# M1_Design.net
KiCad netlist of a schematic drawn in Altium Designer
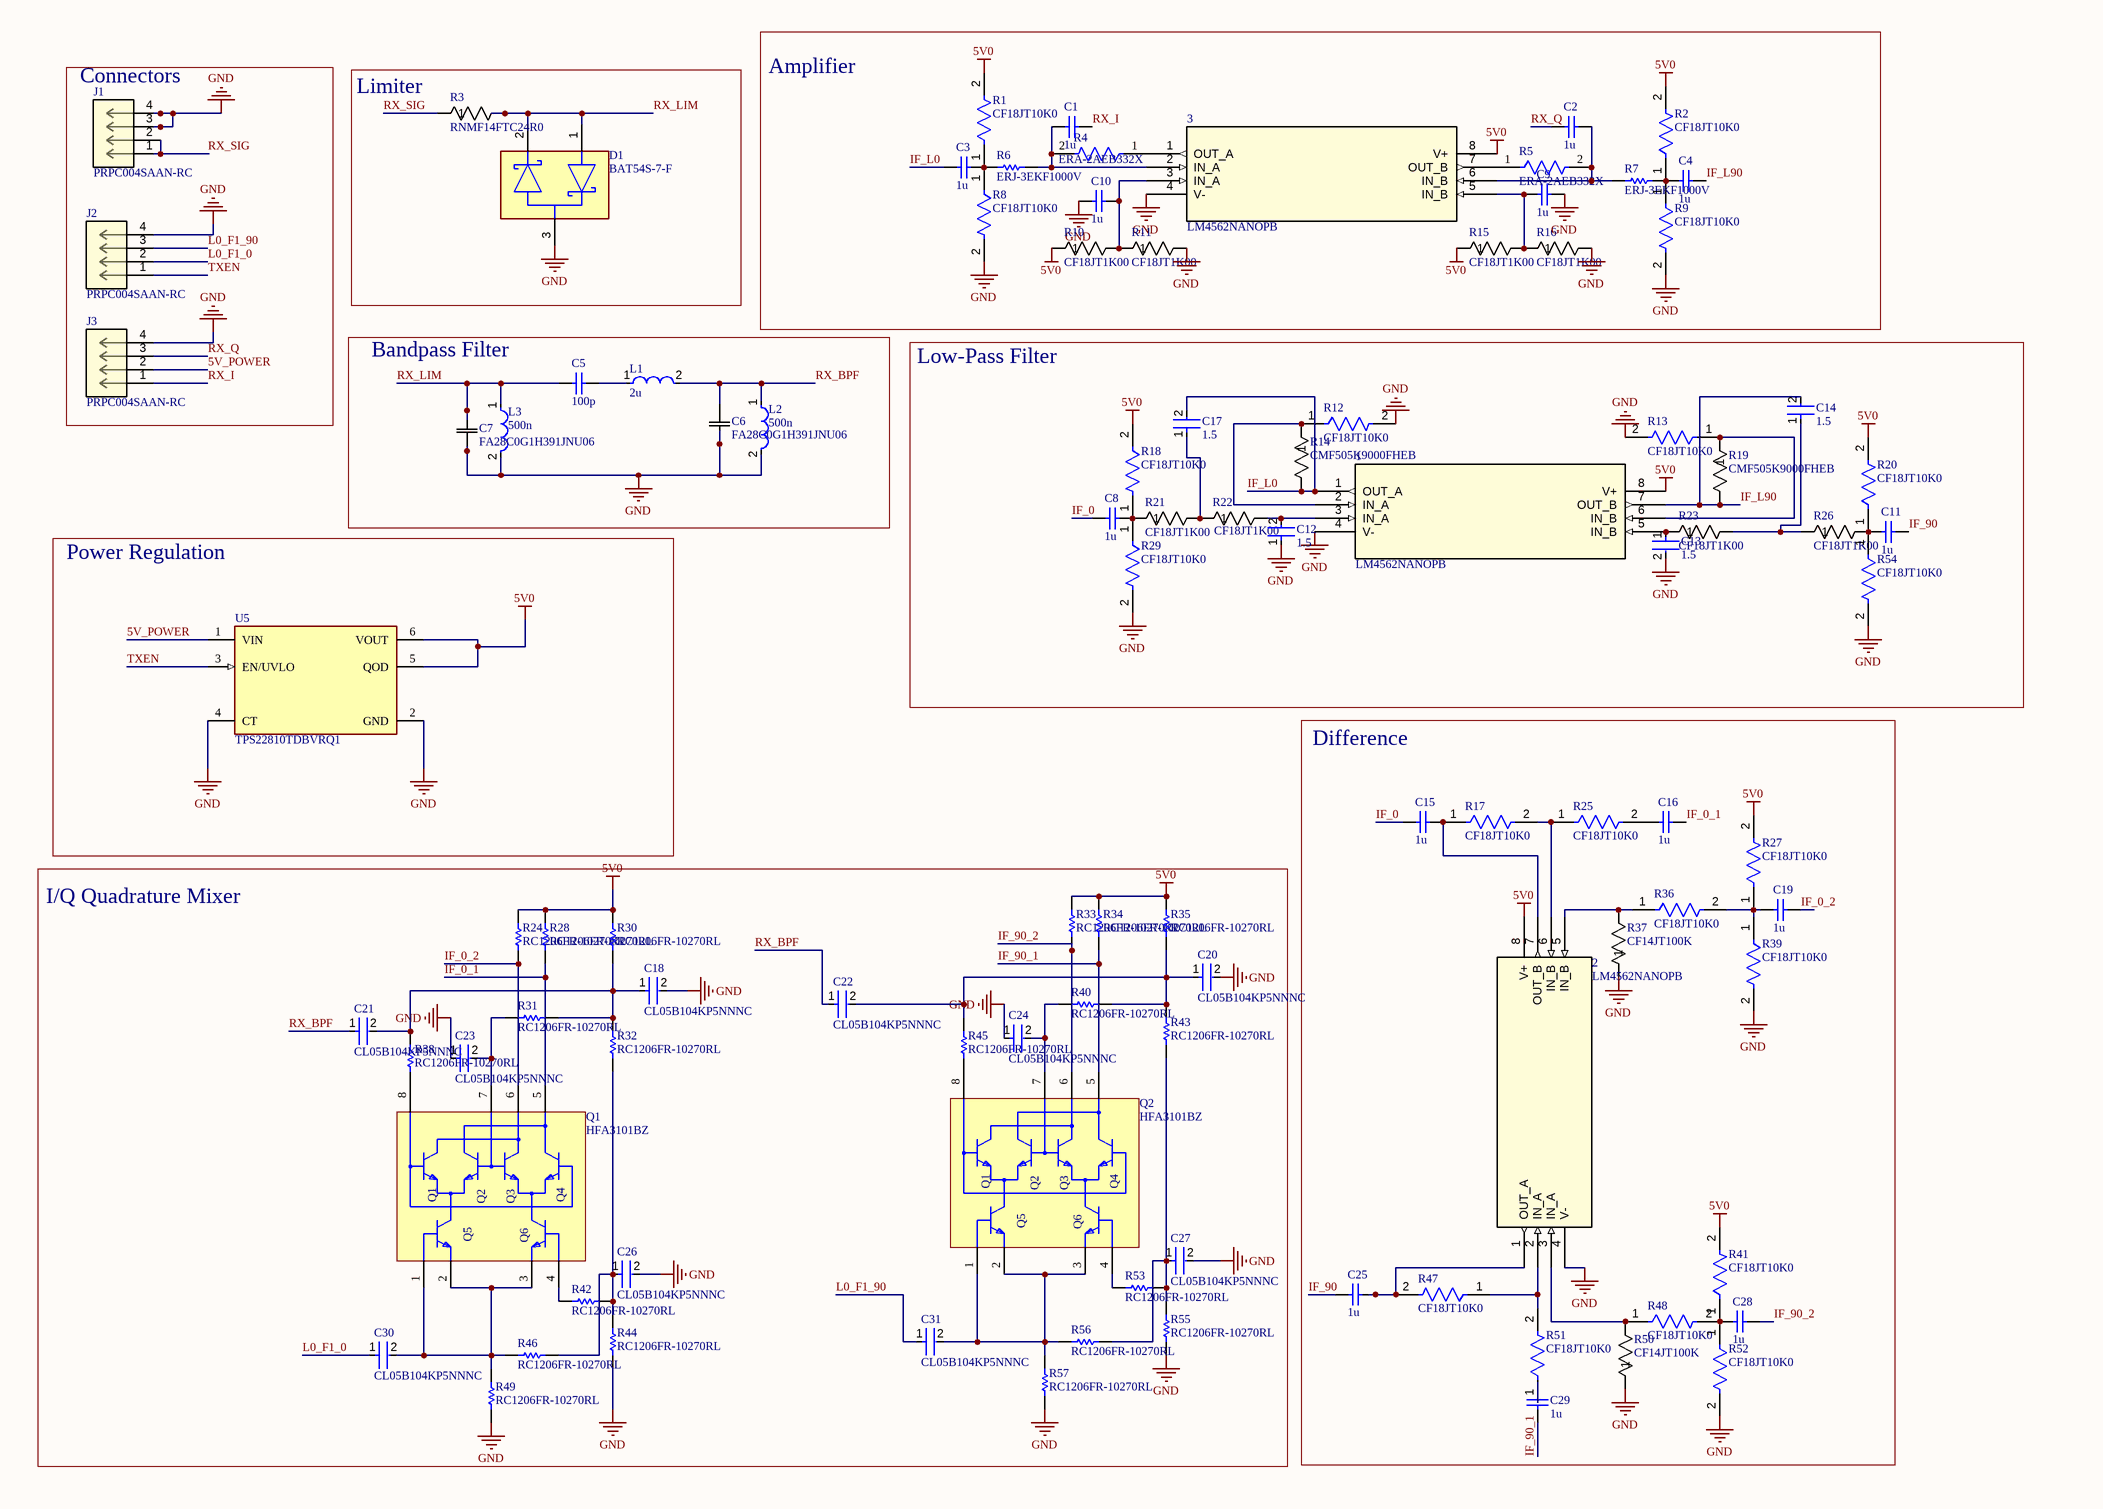
[diagram p0: M1 Design.SchDoc]

(export (version "E")
  (design (tool "Eeschema 10.0.6"))
  (components
    (comp (ref "1")
      (value "LM4562NANOPB")
      (footprint "N08E")
      (description "No Description Available")
      (libsource (lib "LM4562NANOPB") (part "LM4562NANOPB"))
    )
    (comp (ref "2")
      (value "LM4562NANOPB")
      (footprint "N08E")
      (description "No Description Available")
      (libsource (lib "") (part "LM4562NANOPB_1"))
    )
    (comp (ref "3")
      (value "LM4562NANOPB")
      (footprint "N08E")
      (description "No Description Available")
      (libsource (lib "LM4562NANOPB") (part "LM4562NANOPB"))
    )
    (comp (ref "C1")
      (value "1u")
      (footprint "CAPC3216X110X50LL20T25")
      (description "Chip Capacitor, 1 uF, +/- 10%, 50 V, -55 to 125 degC, 1206 (3216 Metric), RoHS, Tape and Reel")
      (fields (field (name "MANUFACTURER") "Kemet") (field (name "TOLERANCE") "10%"))
      (libsource (lib "Altium Content Vault") (part "CAP-NP-2"))
    )
    (comp (ref "C2")
      (value "1u")
      (footprint "CAPC3216X110X50LL20T25")
      (description "Chip Capacitor, 1 uF, +/- 10%, 50 V, -55 to 125 degC, 1206 (3216 Metric), RoHS, Tape and Reel")
      (fields (field (name "MANUFACTURER") "Kemet") (field (name "TOLERANCE") "10%"))
      (libsource (lib "Altium Content Vault") (part "CAP-NP-2"))
    )
    (comp (ref "C3")
      (value "1u")
      (footprint "CAPC3216X110X50LL20T25")
      (description "Chip Capacitor, 1 uF, +/- 10%, 50 V, -55 to 125 degC, 1206 (3216 Metric), RoHS, Tape and Reel")
      (fields (field (name "MANUFACTURER") "Kemet") (field (name "TOLERANCE") "10%"))
      (libsource (lib "Altium Content Vault") (part "CAP-NP-2"))
    )
    (comp (ref "C4")
      (value "1u")
      (footprint "CAPC3216X110X50LL20T25")
      (description "Chip Capacitor, 1 uF, +/- 10%, 50 V, -55 to 125 degC, 1206 (3216 Metric), RoHS, Tape and Reel")
      (fields (field (name "MANUFACTURER") "Kemet") (field (name "TOLERANCE") "10%"))
      (libsource (lib "Altium Content Vault") (part "CAP-NP-2"))
    )
    (comp (ref "C5")
      (value "100p")
      (footprint "CAPC1608X90X40ML10T20")
      (description "Chip Capacitor, 100 pF, +/- 5%, 50 V, -55 to 125 degC, 0603 (1608 Metric), RoHS, Tape and Reel")
      (fields (field (name "TOLERANCE") "5%") (field (name "VOLTAGE") "50V"))
      (libsource (lib "Altium Content Vault") (part "CAP-NP-2"))
    )
    (comp (ref "C6")
      (value "FA28C0G1H391JNU06")
      (footprint "CAP_FA28_TDK")
      (description "No Description Available")
      (libsource (lib "FA28C0G1H391JNU06") (part "FA28C0G1H391JNU06"))
    )
    (comp (ref "C7")
      (value "FA28C0G1H391JNU06")
      (footprint "CAP_FA28_TDK")
      (description "No Description Available")
      (libsource (lib "FA28C0G1H391JNU06") (part "FA28C0G1H391JNU06"))
    )
    (comp (ref "C8")
      (value "1u")
      (footprint "CAPC3216X110X50LL20T25")
      (description "Chip Capacitor, 1 uF, +/- 10%, 50 V, -55 to 125 degC, 1206 (3216 Metric), RoHS, Tape and Reel")
      (fields (field (name "MANUFACTURER") "Kemet") (field (name "TOLERANCE") "10%"))
      (libsource (lib "Altium Content Vault") (part "CAP-NP-2"))
    )
    (comp (ref "C9")
      (value "1u")
      (footprint "CAPC3216X110X50LL20T25")
      (description "Chip Capacitor, 1 uF, +/- 10%, 50 V, -55 to 125 degC, 1206 (3216 Metric), RoHS, Tape and Reel")
      (fields (field (name "MANUFACTURER") "Kemet") (field (name "TOLERANCE") "10%"))
      (libsource (lib "Altium Content Vault") (part "CAP-NP-2"))
    )
    (comp (ref "C10")
      (value "1u")
      (footprint "CAPC3216X110X50LL20T25")
      (description "Chip Capacitor, 1 uF, +/- 10%, 50 V, -55 to 125 degC, 1206 (3216 Metric), RoHS, Tape and Reel")
      (fields (field (name "MANUFACTURER") "Kemet") (field (name "TOLERANCE") "10%"))
      (libsource (lib "Altium Content Vault") (part "CAP-NP-2"))
    )
    (comp (ref "C11")
      (value "1u")
      (footprint "CAPC3216X110X50LL20T25")
      (description "Chip Capacitor, 1 uF, +/- 10%, 50 V, -55 to 125 degC, 1206 (3216 Metric), RoHS, Tape and Reel")
      (fields (field (name "MANUFACTURER") "Kemet") (field (name "TOLERANCE") "10%"))
      (libsource (lib "Altium Content Vault") (part "CAP-NP-2"))
    )
    (comp (ref "C12")
      (value "1.5")
      (footprint "FP-C0402-BB-MFG")
      (description "CAP CER 1500PF 50V NP0 0402")
      (fields
        (field (name "OCTOPART") "https://octopart.com/c0402c152j5gactu-kemet-12793166")
        (field (name "MANUFACTURER PART NUMBER") "C0402C152J5GACTU")
      )
      (libsource (lib "Altium Content Vault") (part "b4654b650e69147ec39a6b967a45e02"))
    )
    (comp (ref "C13")
      (value "1.5")
      (footprint "FP-C0402-BB-MFG")
      (description "CAP CER 1500PF 50V NP0 0402")
      (fields
        (field (name "OCTOPART") "https://octopart.com/c0402c152j5gactu-kemet-12793166")
        (field (name "MANUFACTURER PART NUMBER") "C0402C152J5GACTU")
      )
      (libsource (lib "Altium Content Vault") (part "b4654b650e69147ec39a6b967a45e02"))
    )
    (comp (ref "C14")
      (value "1.5")
      (footprint "FP-C0402-BB-MFG")
      (description "CAP CER 1500PF 50V NP0 0402")
      (fields
        (field (name "OCTOPART") "https://octopart.com/c0402c152j5gactu-kemet-12793166")
        (field (name "MANUFACTURER PART NUMBER") "C0402C152J5GACTU")
      )
      (libsource (lib "Altium Content Vault") (part "b4654b650e69147ec39a6b967a45e02"))
    )
    (comp (ref "C15")
      (value "1u")
      (footprint "CAPC3216X110X50LL20T25")
      (description "Chip Capacitor, 1 uF, +/- 10%, 50 V, -55 to 125 degC, 1206 (3216 Metric), RoHS, Tape and Reel")
      (fields (field (name "MANUFACTURER") "Kemet") (field (name "TOLERANCE") "10%"))
      (libsource (lib "Altium Content Vault") (part "CAP-NP-2"))
    )
    (comp (ref "C16")
      (value "1u")
      (footprint "CAPC3216X110X50LL20T25")
      (description "Chip Capacitor, 1 uF, +/- 10%, 50 V, -55 to 125 degC, 1206 (3216 Metric), RoHS, Tape and Reel")
      (fields (field (name "MANUFACTURER") "Kemet") (field (name "TOLERANCE") "10%"))
      (libsource (lib "Altium Content Vault") (part "CAP-NP-2"))
    )
    (comp (ref "C17")
      (value "1.5")
      (footprint "FP-C0402-BB-MFG")
      (description "CAP CER 1500PF 50V NP0 0402")
      (fields
        (field (name "OCTOPART") "https://octopart.com/c0402c152j5gactu-kemet-12793166")
        (field (name "MANUFACTURER PART NUMBER") "C0402C152J5GACTU")
      )
      (libsource (lib "Altium Content Vault") (part "b4654b650e69147ec39a6b967a45e02"))
    )
    (comp (ref "C18")
      (value "CL05B104KP5NNNC")
      (footprint "FP-CL17-IPC_C")
      (description "Cap Ceramic 100nF 10V X7R ±10% SMD 0402 +125°C Paper T/R")
      (fields (field (name "TOLERANCE") "10%"))
      (libsource (lib "Altium Content Vault") (part "b4654b650e69147ec39a6b967a45e02"))
    )
    (comp (ref "C19")
      (value "1u")
      (footprint "CAPC3216X110X50LL20T25")
      (description "Chip Capacitor, 1 uF, +/- 10%, 50 V, -55 to 125 degC, 1206 (3216 Metric), RoHS, Tape and Reel")
      (fields (field (name "MANUFACTURER") "Kemet") (field (name "TOLERANCE") "10%"))
      (libsource (lib "Altium Content Vault") (part "CAP-NP-2"))
    )
    (comp (ref "C20")
      (value "CL05B104KP5NNNC")
      (footprint "FP-CL17-IPC_C")
      (description "Cap Ceramic 100nF 10V X7R ±10% SMD 0402 +125°C Paper T/R")
      (fields (field (name "TOLERANCE") "10%"))
      (libsource (lib "Altium Content Vault") (part "b4654b650e69147ec39a6b967a45e02"))
    )
    (comp (ref "C21")
      (value "CL05B104KP5NNNC")
      (footprint "FP-CL17-IPC_C")
      (description "Cap Ceramic 100nF 10V X7R ±10% SMD 0402 +125°C Paper T/R")
      (fields (field (name "TOLERANCE") "10%"))
      (libsource (lib "Altium Content Vault") (part "b4654b650e69147ec39a6b967a45e02"))
    )
    (comp (ref "C22")
      (value "CL05B104KP5NNNC")
      (footprint "FP-CL17-IPC_C")
      (description "Cap Ceramic 100nF 10V X7R ±10% SMD 0402 +125°C Paper T/R")
      (fields (field (name "TOLERANCE") "10%"))
      (libsource (lib "Altium Content Vault") (part "b4654b650e69147ec39a6b967a45e02"))
    )
    (comp (ref "C23")
      (value "CL05B104KP5NNNC")
      (footprint "FP-CL17-IPC_C")
      (description "Cap Ceramic 100nF 10V X7R ±10% SMD 0402 +125°C Paper T/R")
      (fields (field (name "TOLERANCE") "10%"))
      (libsource (lib "Altium Content Vault") (part "b4654b650e69147ec39a6b967a45e02"))
    )
    (comp (ref "C24")
      (value "CL05B104KP5NNNC")
      (footprint "FP-CL17-IPC_C")
      (description "Cap Ceramic 100nF 10V X7R ±10% SMD 0402 +125°C Paper T/R")
      (fields (field (name "TOLERANCE") "10%"))
      (libsource (lib "Altium Content Vault") (part "b4654b650e69147ec39a6b967a45e02"))
    )
    (comp (ref "C25")
      (value "1u")
      (footprint "CAPC3216X110X50LL20T25")
      (description "Chip Capacitor, 1 uF, +/- 10%, 50 V, -55 to 125 degC, 1206 (3216 Metric), RoHS, Tape and Reel")
      (fields (field (name "MANUFACTURER") "Kemet") (field (name "TOLERANCE") "10%"))
      (libsource (lib "Altium Content Vault") (part "CAP-NP-2"))
    )
    (comp (ref "C26")
      (value "CL05B104KP5NNNC")
      (footprint "FP-CL17-IPC_C")
      (description "Cap Ceramic 100nF 10V X7R ±10% SMD 0402 +125°C Paper T/R")
      (fields (field (name "TOLERANCE") "10%"))
      (libsource (lib "Altium Content Vault") (part "b4654b650e69147ec39a6b967a45e02"))
    )
    (comp (ref "C27")
      (value "CL05B104KP5NNNC")
      (footprint "FP-CL17-IPC_C")
      (description "Cap Ceramic 100nF 10V X7R ±10% SMD 0402 +125°C Paper T/R")
      (fields (field (name "TOLERANCE") "10%"))
      (libsource (lib "Altium Content Vault") (part "b4654b650e69147ec39a6b967a45e02"))
    )
    (comp (ref "C28")
      (value "1u")
      (footprint "CAPC3216X110X50LL20T25")
      (description "Chip Capacitor, 1 uF, +/- 10%, 50 V, -55 to 125 degC, 1206 (3216 Metric), RoHS, Tape and Reel")
      (fields (field (name "MANUFACTURER") "Kemet") (field (name "TOLERANCE") "10%"))
      (libsource (lib "Altium Content Vault") (part "CAP-NP-2"))
    )
    (comp (ref "C29")
      (value "1u")
      (footprint "CAPC3216X110X50LL20T25")
      (description "Chip Capacitor, 1 uF, +/- 10%, 50 V, -55 to 125 degC, 1206 (3216 Metric), RoHS, Tape and Reel")
      (fields (field (name "MANUFACTURER") "Kemet") (field (name "TOLERANCE") "10%"))
      (libsource (lib "Altium Content Vault") (part "CAP-NP-2"))
    )
    (comp (ref "C30")
      (value "CL05B104KP5NNNC")
      (footprint "FP-CL17-IPC_C")
      (description "Cap Ceramic 100nF 10V X7R ±10% SMD 0402 +125°C Paper T/R")
      (fields (field (name "TOLERANCE") "10%"))
      (libsource (lib "Altium Content Vault") (part "b4654b650e69147ec39a6b967a45e02"))
    )
    (comp (ref "C31")
      (value "CL05B104KP5NNNC")
      (footprint "FP-CL17-IPC_C")
      (description "Cap Ceramic 100nF 10V X7R ±10% SMD 0402 +125°C Paper T/R")
      (fields (field (name "TOLERANCE") "10%"))
      (libsource (lib "Altium Content Vault") (part "b4654b650e69147ec39a6b967a45e02"))
    )
    (comp (ref "D1")
      (value "BAT54S-7-F")
      (footprint "FP-SOT23-MFG")
      (description "DIODE ARRAY SCHOTTKY 30V SOT23-3")
      (libsource (lib "Altium Content Vault") (part "835e4e71cf852b8cae3cf70bf14abf8"))
    )
    (comp (ref "J1")
      (value "PRPC004SAAN-RC")
      (footprint "CONN4_PRPC004_SUL")
      (description "No Description Available")
      (libsource (lib "PRPC004SAAN-RC") (part "PRPC004SAAN-RC"))
    )
    (comp (ref "J2")
      (value "PRPC004SAAN-RC")
      (footprint "CONN4_PRPC004_SUL")
      (description "No Description Available")
      (libsource (lib "PRPC004SAAN-RC") (part "PRPC004SAAN-RC"))
    )
    (comp (ref "J3")
      (value "PRPC004SAAN-RC")
      (footprint "CONN4_PRPC004_SUL")
      (description "No Description Available")
      (libsource (lib "PRPC004SAAN-RC") (part "PRPC004SAAN-RC"))
    )
    (comp (ref "L1")
      (value "2u")
      (footprint "FP-LQW15CA_00-MFG")
      (description "Wire Wound Ferrite Inductor for General Circuits 2000nH ±10% 130mA 3.2Ω 0402 (1005)")
      (fields (field (name "TOLERANCE") "10%"))
      (libsource (lib "Altium Content Vault") (part "725321dda6339637d4d059423bc1c3c"))
    )
    (comp (ref "L2")
      (value "500n")
      (footprint "FP-LQW15CA_00-MFG")
      (description "Wire Wound Ferrite Inductor for General Circuits 500nH ±5% 270mA 0.97Ω 0402 (1005)")
      (fields (field (name "TOLERANCE") "5%"))
      (libsource (lib "Altium Content Vault") (part "725321dda6339637d4d059423bc1c3c"))
    )
    (comp (ref "L3")
      (value "500n")
      (footprint "FP-LQW15CA_00-MFG")
      (description "Wire Wound Ferrite Inductor for General Circuits 500nH ±5% 270mA 0.97Ω 0402 (1005)")
      (fields (field (name "TOLERANCE") "5%"))
      (libsource (lib "Altium Content Vault") (part "725321dda6339637d4d059423bc1c3c"))
    )
    (comp (ref "Q1")
      (value "HFA3101BZ")
      (footprint "M8_15_MFG")
      (description "HFA3096 Series NPN 12 Vce 10 Ghz UHF Transistor Array - SOIC-8")
      (libsource (lib "Altium Content Vault") (part "bc79141c5fe5962b3618e6c48c8dfa3"))
    )
    (comp (ref "Q2")
      (value "HFA3101BZ")
      (footprint "M8_15_MFG")
      (description "HFA3096 Series NPN 12 Vce 10 Ghz UHF Transistor Array - SOIC-8")
      (libsource (lib "Altium Content Vault") (part "bc79141c5fe5962b3618e6c48c8dfa3"))
    )
    (comp (ref "R1")
      (value "CF18JT10K0")
      (footprint "FP-CF18-MFG")
      (description "RES 10K OHM 1/8W 5% CF AXIAL")
      (fields
        (field (name "MANUFACTURER") "Stackpole Electronics")
        (field (name "OCTOPART") "https://octopart.com/cf18jt10k0-stackpole+electronics-19205642")
      )
      (libsource (lib "Altium Content Vault") (part "1029c3af85768c4190bb7ad29bc67b5"))
    )
    (comp (ref "R2")
      (value "CF18JT10K0")
      (footprint "FP-CF18-MFG")
      (description "RES 10K OHM 1/8W 5% CF AXIAL")
      (fields
        (field (name "MANUFACTURER") "Stackpole Electronics")
        (field (name "OCTOPART") "https://octopart.com/cf18jt10k0-stackpole+electronics-19205642")
      )
      (libsource (lib "Altium Content Vault") (part "1029c3af85768c4190bb7ad29bc67b5"))
    )
    (comp (ref "R3")
      (value "RNMF14FTC24R0")
      (footprint "STA_RNMF14_STP")
      (description "No Description Available")
      (libsource (lib "RNMF14FTC24R0") (part "RNMF14FTC24R0"))
    )
    (comp (ref "R4")
      (value "ERA-2AEB332X")
      (footprint "FP-ERA2A-MFG")
      (fields (field (name "TOLERANCE") "0.1%"))
      (libsource (lib "Altium Content Vault") (part "1029c3af85768c4190bb7ad29bc67b5"))
    )
    (comp (ref "R5")
      (value "ERA-2AEB332X")
      (footprint "FP-ERA2A-MFG")
      (fields (field (name "TOLERANCE") "0.1%"))
      (libsource (lib "Altium Content Vault") (part "1029c3af85768c4190bb7ad29bc67b5"))
    )
    (comp (ref "R6")
      (value "ERJ-3EKF1000V")
      (footprint "RESC1608X55X30LL15T15")
      (fields (field (name "MANUFACTURER") "Panasonic"))
      (libsource (lib "Altium Content Vault") (part "RES"))
    )
    (comp (ref "R7")
      (value "ERJ-3EKF1000V")
      (footprint "RESC1608X55X30LL15T15")
      (fields (field (name "MANUFACTURER") "Panasonic"))
      (libsource (lib "Altium Content Vault") (part "RES"))
    )
    (comp (ref "R8")
      (value "CF18JT10K0")
      (footprint "FP-CF18-MFG")
      (description "RES 10K OHM 1/8W 5% CF AXIAL")
      (fields
        (field (name "MANUFACTURER") "Stackpole Electronics")
        (field (name "OCTOPART") "https://octopart.com/cf18jt10k0-stackpole+electronics-19205642")
      )
      (libsource (lib "Altium Content Vault") (part "1029c3af85768c4190bb7ad29bc67b5"))
    )
    (comp (ref "R9")
      (value "CF18JT10K0")
      (footprint "FP-CF18-MFG")
      (description "RES 10K OHM 1/8W 5% CF AXIAL")
      (fields
        (field (name "MANUFACTURER") "Stackpole Electronics")
        (field (name "OCTOPART") "https://octopart.com/cf18jt10k0-stackpole+electronics-19205642")
      )
      (libsource (lib "Altium Content Vault") (part "1029c3af85768c4190bb7ad29bc67b5"))
    )
    (comp (ref "R10")
      (value "CF18JT1K00")
      (footprint "STA_CF18_STP")
      (description "No Description Available")
      (libsource (lib "CF18JT1K00") (part "CF18JT1K00"))
    )
    (comp (ref "R11")
      (value "CF18JT1K00")
      (footprint "STA_CF18_STP")
      (description "No Description Available")
      (libsource (lib "CF18JT1K00") (part "CF18JT1K00"))
    )
    (comp (ref "R12")
      (value "CF18JT10K0")
      (footprint "FP-CF18-MFG")
      (description "RES 10K OHM 1/8W 5% CF AXIAL")
      (fields
        (field (name "MANUFACTURER") "Stackpole Electronics")
        (field (name "OCTOPART") "https://octopart.com/cf18jt10k0-stackpole+electronics-19205642")
      )
      (libsource (lib "Altium Content Vault") (part "1029c3af85768c4190bb7ad29bc67b5"))
    )
    (comp (ref "R13")
      (value "CF18JT10K0")
      (footprint "FP-CF18-MFG")
      (description "RES 10K OHM 1/8W 5% CF AXIAL")
      (fields
        (field (name "MANUFACTURER") "Stackpole Electronics")
        (field (name "OCTOPART") "https://octopart.com/cf18jt10k0-stackpole+electronics-19205642")
      )
      (libsource (lib "Altium Content Vault") (part "1029c3af85768c4190bb7ad29bc67b5"))
    )
    (comp (ref "R14")
      (value "CMF505K9000FHEB")
      (footprint "RES_CMF50_VIS")
      (description "No Description Available")
      (libsource (lib "CMF505K9000FHEB") (part "CMF505K9000FHEB"))
    )
    (comp (ref "R15")
      (value "CF18JT1K00")
      (footprint "STA_CF18_STP")
      (description "No Description Available")
      (libsource (lib "CF18JT1K00") (part "CF18JT1K00"))
    )
    (comp (ref "R16")
      (value "CF18JT1K00")
      (footprint "STA_CF18_STP")
      (description "No Description Available")
      (libsource (lib "CF18JT1K00") (part "CF18JT1K00"))
    )
    (comp (ref "R17")
      (value "CF18JT10K0")
      (footprint "FP-CF18-MFG")
      (description "RES 10K OHM 1/8W 5% CF AXIAL")
      (fields
        (field (name "MANUFACTURER") "Stackpole Electronics")
        (field (name "OCTOPART") "https://octopart.com/cf18jt10k0-stackpole+electronics-19205642")
      )
      (libsource (lib "Altium Content Vault") (part "1029c3af85768c4190bb7ad29bc67b5"))
    )
    (comp (ref "R18")
      (value "CF18JT10K0")
      (footprint "FP-CF18-MFG")
      (description "RES 10K OHM 1/8W 5% CF AXIAL")
      (fields
        (field (name "MANUFACTURER") "Stackpole Electronics")
        (field (name "OCTOPART") "https://octopart.com/cf18jt10k0-stackpole+electronics-19205642")
      )
      (libsource (lib "") (part "1029c3af85768c4190bb7ad29bc67b5_1"))
    )
    (comp (ref "R19")
      (value "CMF505K9000FHEB")
      (footprint "RES_CMF50_VIS")
      (description "No Description Available")
      (libsource (lib "CMF505K9000FHEB") (part "CMF505K9000FHEB"))
    )
    (comp (ref "R20")
      (value "CF18JT10K0")
      (footprint "FP-CF18-MFG")
      (description "RES 10K OHM 1/8W 5% CF AXIAL")
      (fields
        (field (name "MANUFACTURER") "Stackpole Electronics")
        (field (name "OCTOPART") "https://octopart.com/cf18jt10k0-stackpole+electronics-19205642")
      )
      (libsource (lib "Altium Content Vault") (part "1029c3af85768c4190bb7ad29bc67b5"))
    )
    (comp (ref "R21")
      (value "CF18JT1K00")
      (footprint "STA_CF18_STP")
      (description "No Description Available")
      (libsource (lib "CF18JT1K00") (part "CF18JT1K00"))
    )
    (comp (ref "R22")
      (value "CF18JT1K00")
      (footprint "STA_CF18_STP")
      (description "No Description Available")
      (libsource (lib "CF18JT1K00") (part "CF18JT1K00"))
    )
    (comp (ref "R23")
      (value "CF18JT1K00")
      (footprint "STA_CF18_STP")
      (description "No Description Available")
      (libsource (lib "CF18JT1K00") (part "CF18JT1K00"))
    )
    (comp (ref "R24")
      (value "RC1206FR-10270RL")
      (footprint "RESC3116X65X40NL10T20")
      (fields (field (name "MANUFACTURER") "Yageo"))
      (libsource (lib "Altium Content Vault") (part "RES"))
    )
    (comp (ref "R25")
      (value "CF18JT10K0")
      (footprint "FP-CF18-MFG")
      (description "RES 10K OHM 1/8W 5% CF AXIAL")
      (fields
        (field (name "MANUFACTURER") "Stackpole Electronics")
        (field (name "OCTOPART") "https://octopart.com/cf18jt10k0-stackpole+electronics-19205642")
      )
      (libsource (lib "Altium Content Vault") (part "1029c3af85768c4190bb7ad29bc67b5"))
    )
    (comp (ref "R26")
      (value "CF18JT1K00")
      (footprint "STA_CF18_STP")
      (description "No Description Available")
      (libsource (lib "CF18JT1K00") (part "CF18JT1K00"))
    )
    (comp (ref "R27")
      (value "CF18JT10K0")
      (footprint "FP-CF18-MFG")
      (description "RES 10K OHM 1/8W 5% CF AXIAL")
      (fields
        (field (name "MANUFACTURER") "Stackpole Electronics")
        (field (name "OCTOPART") "https://octopart.com/cf18jt10k0-stackpole+electronics-19205642")
      )
      (libsource (lib "Altium Content Vault") (part "1029c3af85768c4190bb7ad29bc67b5"))
    )
    (comp (ref "R28")
      (value "RC1206FR-10270RL")
      (footprint "RESC3116X65X40NL10T20")
      (fields (field (name "MANUFACTURER") "Yageo"))
      (libsource (lib "Altium Content Vault") (part "RES"))
    )
    (comp (ref "R29")
      (value "CF18JT10K0")
      (footprint "FP-CF18-MFG")
      (description "RES 10K OHM 1/8W 5% CF AXIAL")
      (fields
        (field (name "MANUFACTURER") "Stackpole Electronics")
        (field (name "OCTOPART") "https://octopart.com/cf18jt10k0-stackpole+electronics-19205642")
      )
      (libsource (lib "Altium Content Vault") (part "1029c3af85768c4190bb7ad29bc67b5"))
    )
    (comp (ref "R30")
      (value "RC1206FR-10270RL")
      (footprint "RESC3116X65X40NL10T20")
      (fields (field (name "MANUFACTURER") "Yageo"))
      (libsource (lib "Altium Content Vault") (part "RES"))
    )
    (comp (ref "R31")
      (value "RC1206FR-10270RL")
      (footprint "RESC3116X65X40NL10T20")
      (fields (field (name "MANUFACTURER") "Yageo"))
      (libsource (lib "Altium Content Vault") (part "RES"))
    )
    (comp (ref "R32")
      (value "RC1206FR-10270RL")
      (footprint "RESC3116X65X40NL10T20")
      (fields (field (name "MANUFACTURER") "Yageo"))
      (libsource (lib "Altium Content Vault") (part "RES"))
    )
    (comp (ref "R33")
      (value "RC1206FR-10270RL")
      (footprint "RESC3116X65X40NL10T20")
      (fields (field (name "MANUFACTURER") "Yageo"))
      (libsource (lib "Altium Content Vault") (part "RES"))
    )
    (comp (ref "R34")
      (value "RC1206FR-10270RL")
      (footprint "RESC3116X65X40NL10T20")
      (fields (field (name "MANUFACTURER") "Yageo"))
      (libsource (lib "Altium Content Vault") (part "RES"))
    )
    (comp (ref "R35")
      (value "RC1206FR-10270RL")
      (footprint "RESC3116X65X40NL10T20")
      (fields (field (name "MANUFACTURER") "Yageo"))
      (libsource (lib "Altium Content Vault") (part "RES"))
    )
    (comp (ref "R36")
      (value "CF18JT10K0")
      (footprint "FP-CF18-MFG")
      (description "RES 10K OHM 1/8W 5% CF AXIAL")
      (fields
        (field (name "MANUFACTURER") "Stackpole Electronics")
        (field (name "OCTOPART") "https://octopart.com/cf18jt10k0-stackpole+electronics-19205642")
      )
      (libsource (lib "Altium Content Vault") (part "1029c3af85768c4190bb7ad29bc67b5"))
    )
    (comp (ref "R37")
      (value "CF14JT100K")
      (footprint "STA_CF14_STP")
      (description "No Description Available")
      (libsource (lib "CF14JT100K") (part "CF14JT100K"))
    )
    (comp (ref "R38")
      (value "RC1206FR-10270RL")
      (footprint "RESC3116X65X40NL10T20")
      (fields (field (name "MANUFACTURER") "Yageo"))
      (libsource (lib "Altium Content Vault") (part "RES"))
    )
    (comp (ref "R39")
      (value "CF18JT10K0")
      (footprint "FP-CF18-MFG")
      (description "RES 10K OHM 1/8W 5% CF AXIAL")
      (fields
        (field (name "MANUFACTURER") "Stackpole Electronics")
        (field (name "OCTOPART") "https://octopart.com/cf18jt10k0-stackpole+electronics-19205642")
      )
      (libsource (lib "Altium Content Vault") (part "1029c3af85768c4190bb7ad29bc67b5"))
    )
    (comp (ref "R40")
      (value "RC1206FR-10270RL")
      (footprint "RESC3116X65X40NL10T20")
      (fields (field (name "MANUFACTURER") "Yageo"))
      (libsource (lib "Altium Content Vault") (part "RES"))
    )
    (comp (ref "R41")
      (value "CF18JT10K0")
      (footprint "FP-CF18-MFG")
      (description "RES 10K OHM 1/8W 5% CF AXIAL")
      (fields
        (field (name "MANUFACTURER") "Stackpole Electronics")
        (field (name "OCTOPART") "https://octopart.com/cf18jt10k0-stackpole+electronics-19205642")
      )
      (libsource (lib "Altium Content Vault") (part "1029c3af85768c4190bb7ad29bc67b5"))
    )
    (comp (ref "R42")
      (value "RC1206FR-10270RL")
      (footprint "RESC3116X65X40NL10T20")
      (fields (field (name "MANUFACTURER") "Yageo"))
      (libsource (lib "Altium Content Vault") (part "RES"))
    )
    (comp (ref "R43")
      (value "RC1206FR-10270RL")
      (footprint "RESC3116X65X40NL10T20")
      (fields (field (name "MANUFACTURER") "Yageo"))
      (libsource (lib "Altium Content Vault") (part "RES"))
    )
    (comp (ref "R44")
      (value "RC1206FR-10270RL")
      (footprint "RESC3116X65X40NL10T20")
      (fields (field (name "MANUFACTURER") "Yageo"))
      (libsource (lib "Altium Content Vault") (part "RES"))
    )
    (comp (ref "R45")
      (value "RC1206FR-10270RL")
      (footprint "RESC3116X65X40NL10T20")
      (fields (field (name "MANUFACTURER") "Yageo"))
      (libsource (lib "Altium Content Vault") (part "RES"))
    )
    (comp (ref "R46")
      (value "RC1206FR-10270RL")
      (footprint "RESC3116X65X40NL10T20")
      (fields (field (name "MANUFACTURER") "Yageo"))
      (libsource (lib "Altium Content Vault") (part "RES"))
    )
    (comp (ref "R47")
      (value "CF18JT10K0")
      (footprint "FP-CF18-MFG")
      (description "RES 10K OHM 1/8W 5% CF AXIAL")
      (fields
        (field (name "MANUFACTURER") "Stackpole Electronics")
        (field (name "OCTOPART") "https://octopart.com/cf18jt10k0-stackpole+electronics-19205642")
      )
      (libsource (lib "Altium Content Vault") (part "1029c3af85768c4190bb7ad29bc67b5"))
    )
    (comp (ref "R48")
      (value "CF18JT10K0")
      (footprint "FP-CF18-MFG")
      (description "RES 10K OHM 1/8W 5% CF AXIAL")
      (fields
        (field (name "MANUFACTURER") "Stackpole Electronics")
        (field (name "OCTOPART") "https://octopart.com/cf18jt10k0-stackpole+electronics-19205642")
      )
      (libsource (lib "Altium Content Vault") (part "1029c3af85768c4190bb7ad29bc67b5"))
    )
    (comp (ref "R49")
      (value "RC1206FR-10270RL")
      (footprint "RESC3116X65X40NL10T20")
      (fields (field (name "MANUFACTURER") "Yageo"))
      (libsource (lib "Altium Content Vault") (part "RES"))
    )
    (comp (ref "R50")
      (value "CF14JT100K")
      (footprint "STA_CF14_STP")
      (description "No Description Available")
      (libsource (lib "CF14JT100K") (part "CF14JT100K"))
    )
    (comp (ref "R51")
      (value "CF18JT10K0")
      (footprint "FP-CF18-MFG")
      (description "RES 10K OHM 1/8W 5% CF AXIAL")
      (fields
        (field (name "MANUFACTURER") "Stackpole Electronics")
        (field (name "OCTOPART") "https://octopart.com/cf18jt10k0-stackpole+electronics-19205642")
      )
      (libsource (lib "Altium Content Vault") (part "1029c3af85768c4190bb7ad29bc67b5"))
    )
    (comp (ref "R52")
      (value "CF18JT10K0")
      (footprint "FP-CF18-MFG")
      (description "RES 10K OHM 1/8W 5% CF AXIAL")
      (fields
        (field (name "MANUFACTURER") "Stackpole Electronics")
        (field (name "OCTOPART") "https://octopart.com/cf18jt10k0-stackpole+electronics-19205642")
      )
      (libsource (lib "Altium Content Vault") (part "1029c3af85768c4190bb7ad29bc67b5"))
    )
    (comp (ref "R53")
      (value "RC1206FR-10270RL")
      (footprint "RESC3116X65X40NL10T20")
      (fields (field (name "MANUFACTURER") "Yageo"))
      (libsource (lib "Altium Content Vault") (part "RES"))
    )
    (comp (ref "R54")
      (value "CF18JT10K0")
      (footprint "FP-CF18-MFG")
      (description "RES 10K OHM 1/8W 5% CF AXIAL")
      (fields
        (field (name "MANUFACTURER") "Stackpole Electronics")
        (field (name "OCTOPART") "https://octopart.com/cf18jt10k0-stackpole+electronics-19205642")
      )
      (libsource (lib "Altium Content Vault") (part "1029c3af85768c4190bb7ad29bc67b5"))
    )
    (comp (ref "R55")
      (value "RC1206FR-10270RL")
      (footprint "RESC3116X65X40NL10T20")
      (fields (field (name "MANUFACTURER") "Yageo"))
      (libsource (lib "Altium Content Vault") (part "RES"))
    )
    (comp (ref "R56")
      (value "RC1206FR-10270RL")
      (footprint "RESC3116X65X40NL10T20")
      (fields (field (name "MANUFACTURER") "Yageo"))
      (libsource (lib "Altium Content Vault") (part "RES"))
    )
    (comp (ref "R57")
      (value "RC1206FR-10270RL")
      (footprint "RESC3116X65X40NL10T20")
      (fields (field (name "MANUFACTURER") "Yageo"))
      (libsource (lib "Altium Content Vault") (part "RES"))
    )
    (comp (ref "U5")
      (value "TPS22810TDBVRQ1")
      (footprint "FP-DBV0006A-MFG")
      (description "IC PWR SWITCH N-CHAN 1:1 SOT23-6")
      (libsource (lib "Altium Content Vault") (part "2d4a2501f31e6718a49a06b44f8b6c7"))
    )
  )
  (nets
    (net (code "1") (name "/5V_POWER") (class "Default")
      (node (ref "J3") (pin "2") (pinfunction "2_2") (pintype "passive"))
      (node (ref "U5") (pin "1") (pinfunction "VIN_1") (pintype "power_in"))
    )
    (net (code "2") (name "/IF_0") (class "Default")
      (node (ref "C15") (pin "1") (pinfunction "1_1") (pintype "passive"))
      (node (ref "C8") (pin "1") (pinfunction "1_1") (pintype "passive"))
    )
    (net (code "3") (name "/IF_0_1") (class "Default")
      (node (ref "C16") (pin "2") (pinfunction "2_2") (pintype "passive"))
      (node (ref "Q1") (pin "5") (pinfunction "C2_C4_5") (pintype "passive"))
      (node (ref "R28") (pin "1") (pinfunction "1_1") (pintype "passive"))
    )
    (net (code "4") (name "/IF_0_2") (class "Default")
      (node (ref "C19") (pin "2") (pinfunction "2_2") (pintype "passive"))
      (node (ref "Q1") (pin "6") (pinfunction "C1_C3_6") (pintype "passive"))
      (node (ref "R24") (pin "1") (pinfunction "1_1") (pintype "passive"))
    )
    (net (code "5") (name "/IF_90") (class "Default")
      (node (ref "C11") (pin "2") (pinfunction "2_2") (pintype "passive"))
      (node (ref "C25") (pin "1") (pinfunction "1_1") (pintype "passive"))
    )
    (net (code "6") (name "/IF_90_1") (class "Default")
      (node (ref "C29") (pin "2") (pinfunction "2_2") (pintype "passive"))
      (node (ref "Q2") (pin "5") (pinfunction "C2_C4_5") (pintype "passive"))
      (node (ref "R34") (pin "1") (pinfunction "1_1") (pintype "passive"))
    )
    (net (code "7") (name "/IF_90_2") (class "Default")
      (node (ref "C28") (pin "2") (pinfunction "2_2") (pintype "passive"))
      (node (ref "Q2") (pin "6") (pinfunction "C1_C3_6") (pintype "passive"))
      (node (ref "R33") (pin "1") (pinfunction "1_1") (pintype "passive"))
    )
    (net (code "8") (name "/IF_L0") (class "Default")
      (node (ref "1") (pin "1") (pinfunction "OUT_A_1") (pintype "output"))
      (node (ref "C17") (pin "2") (pinfunction "2_2") (pintype "passive"))
      (node (ref "C3") (pin "1") (pinfunction "1_1") (pintype "passive"))
      (node (ref "R14") (pin "2") (pinfunction "2_2") (pintype "passive"))
    )
    (net (code "9") (name "/IF_L90") (class "Default")
      (node (ref "1") (pin "7") (pinfunction "OUT_B_7") (pintype "output"))
      (node (ref "C14") (pin "2") (pinfunction "2_2") (pintype "passive"))
      (node (ref "C4") (pin "2") (pinfunction "2_2") (pintype "passive"))
      (node (ref "R19") (pin "2") (pinfunction "2_2") (pintype "passive"))
    )
    (net (code "10") (name "/L0_F1_0") (class "Default")
      (node (ref "C30") (pin "1") (pinfunction "1_1") (pintype "passive"))
      (node (ref "J2") (pin "2") (pinfunction "2_2") (pintype "passive"))
    )
    (net (code "11") (name "/L0_F1_90") (class "Default")
      (node (ref "C31") (pin "1") (pinfunction "1_1") (pintype "passive"))
      (node (ref "J2") (pin "3") (pinfunction "3_3") (pintype "passive"))
    )
    (net (code "12") (name "/RX_BPF") (class "Default")
      (node (ref "C21") (pin "1") (pinfunction "1_1") (pintype "passive"))
      (node (ref "C22") (pin "1") (pinfunction "1_1") (pintype "passive"))
      (node (ref "C6") (pin "2") (pinfunction "2_2") (pintype "passive"))
      (node (ref "L1") (pin "2") (pinfunction "2_2") (pintype "passive"))
      (node (ref "L2") (pin "1") (pinfunction "1_1") (pintype "passive"))
    )
    (net (code "13") (name "/RX_I") (class "Default")
      (node (ref "C1") (pin "2") (pinfunction "2_2") (pintype "passive"))
      (node (ref "J3") (pin "1") (pinfunction "1_1") (pintype "passive"))
    )
    (net (code "14") (name "/RX_LIM") (class "Default")
      (node (ref "C5") (pin "1") (pinfunction "1_1") (pintype "passive"))
      (node (ref "C7") (pin "2") (pinfunction "2_2") (pintype "passive"))
      (node (ref "D1") (pin "1") (pinfunction "1_1") (pintype "passive"))
      (node (ref "D1") (pin "2") (pinfunction "2_2") (pintype "passive"))
      (node (ref "L3") (pin "1") (pinfunction "1_1") (pintype "passive"))
      (node (ref "R3") (pin "2") (pinfunction "2_2") (pintype "passive"))
    )
    (net (code "15") (name "/RX_Q") (class "Default")
      (node (ref "C2") (pin "1") (pinfunction "1_1") (pintype "passive"))
      (node (ref "J3") (pin "3") (pinfunction "3_3") (pintype "passive"))
    )
    (net (code "16") (name "/RX_SIG") (class "Default")
      (node (ref "J1") (pin "1") (pinfunction "1_1") (pintype "passive"))
      (node (ref "J1") (pin "2") (pinfunction "2_2") (pintype "passive"))
      (node (ref "R3") (pin "1") (pinfunction "1_1") (pintype "passive"))
    )
    (net (code "17") (name "/TXEN") (class "Default")
      (node (ref "J2") (pin "1") (pinfunction "1_1") (pintype "passive"))
      (node (ref "U5") (pin "3") (pinfunction "EN/UVLO_3") (pintype "input"))
    )
    (net (code "18") (name "5V0") (class "Default")
      (node (ref "1") (pin "8") (pinfunction "V+_8") (pintype "power_in"))
      (node (ref "2") (pin "8") (pinfunction "V+_8") (pintype "power_in"))
      (node (ref "3") (pin "8") (pinfunction "V+_8") (pintype "power_in"))
      (node (ref "R1") (pin "2") (pinfunction "2_2") (pintype "passive"))
      (node (ref "R10") (pin "1") (pinfunction "1_1") (pintype "passive"))
      (node (ref "R15") (pin "1") (pinfunction "1_1") (pintype "passive"))
      (node (ref "R18") (pin "2") (pinfunction "2_2") (pintype "passive"))
      (node (ref "R2") (pin "2") (pinfunction "2_2") (pintype "passive"))
      (node (ref "R20") (pin "2") (pinfunction "2_2") (pintype "passive"))
      (node (ref "R24") (pin "2") (pinfunction "2_2") (pintype "passive"))
      (node (ref "R27") (pin "2") (pinfunction "2_2") (pintype "passive"))
      (node (ref "R28") (pin "2") (pinfunction "2_2") (pintype "passive"))
      (node (ref "R30") (pin "2") (pinfunction "2_2") (pintype "passive"))
      (node (ref "R33") (pin "2") (pinfunction "2_2") (pintype "passive"))
      (node (ref "R34") (pin "2") (pinfunction "2_2") (pintype "passive"))
      (node (ref "R35") (pin "2") (pinfunction "2_2") (pintype "passive"))
      (node (ref "R41") (pin "2") (pinfunction "2_2") (pintype "passive"))
      (node (ref "U5") (pin "5") (pinfunction "QOD_5") (pintype "passive"))
      (node (ref "U5") (pin "6") (pinfunction "VOUT_6") (pintype "passive"))
    )
    (net (code "19") (name "GND") (class "Default")
      (node (ref "1") (pin "4") (pinfunction "V-_4") (pintype "power_in"))
      (node (ref "2") (pin "4") (pinfunction "V-_4") (pintype "power_in"))
      (node (ref "3") (pin "4") (pinfunction "V-_4") (pintype "power_in"))
      (node (ref "C10") (pin "1") (pinfunction "1_1") (pintype "passive"))
      (node (ref "C12") (pin "1") (pinfunction "1_1") (pintype "passive"))
      (node (ref "C13") (pin "2") (pinfunction "2_2") (pintype "passive"))
      (node (ref "C18") (pin "2") (pinfunction "2_2") (pintype "passive"))
      (node (ref "C20") (pin "2") (pinfunction "2_2") (pintype "passive"))
      (node (ref "C23") (pin "1") (pinfunction "1_1") (pintype "passive"))
      (node (ref "C24") (pin "1") (pinfunction "1_1") (pintype "passive"))
      (node (ref "C26") (pin "2") (pinfunction "2_2") (pintype "passive"))
      (node (ref "C27") (pin "2") (pinfunction "2_2") (pintype "passive"))
      (node (ref "C6") (pin "1") (pinfunction "1_1") (pintype "passive"))
      (node (ref "C7") (pin "1") (pinfunction "1_1") (pintype "passive"))
      (node (ref "C9") (pin "2") (pinfunction "2_2") (pintype "passive"))
      (node (ref "D1") (pin "3") (pinfunction "3_3") (pintype "passive"))
      (node (ref "J1") (pin "3") (pinfunction "3_3") (pintype "passive"))
      (node (ref "J1") (pin "4") (pinfunction "4_4") (pintype "passive"))
      (node (ref "J2") (pin "4") (pinfunction "4_4") (pintype "passive"))
      (node (ref "J3") (pin "4") (pinfunction "4_4") (pintype "passive"))
      (node (ref "L2") (pin "2") (pinfunction "2_2") (pintype "passive"))
      (node (ref "L3") (pin "2") (pinfunction "2_2") (pintype "passive"))
      (node (ref "R11") (pin "2") (pinfunction "2_2") (pintype "passive"))
      (node (ref "R12") (pin "2") (pinfunction "2_2") (pintype "passive"))
      (node (ref "R13") (pin "2") (pinfunction "2_2") (pintype "passive"))
      (node (ref "R16") (pin "2") (pinfunction "2_2") (pintype "passive"))
      (node (ref "R29") (pin "2") (pinfunction "2_2") (pintype "passive"))
      (node (ref "R37") (pin "1") (pinfunction "1_1") (pintype "passive"))
      (node (ref "R39") (pin "2") (pinfunction "2_2") (pintype "passive"))
      (node (ref "R44") (pin "1") (pinfunction "1_1") (pintype "passive"))
      (node (ref "R49") (pin "1") (pinfunction "1_1") (pintype "passive"))
      (node (ref "R50") (pin "1") (pinfunction "1_1") (pintype "passive"))
      (node (ref "R52") (pin "2") (pinfunction "2_2") (pintype "passive"))
      (node (ref "R54") (pin "2") (pinfunction "2_2") (pintype "passive"))
      (node (ref "R55") (pin "1") (pinfunction "1_1") (pintype "passive"))
      (node (ref "R57") (pin "1") (pinfunction "1_1") (pintype "passive"))
      (node (ref "R8") (pin "2") (pinfunction "2_2") (pintype "passive"))
      (node (ref "R9") (pin "2") (pinfunction "2_2") (pintype "passive"))
      (node (ref "U5") (pin "2") (pinfunction "GND_2") (pintype "power_in"))
      (node (ref "U5") (pin "4") (pinfunction "CT_4") (pintype "passive"))
    )
    (net (code "20") (name "Net-(1-IN_A-Pad2)") (class "Default")
      (node (ref "1") (pin "2") (pinfunction "IN_A_2") (pintype "input"))
      (node (ref "R12") (pin "1") (pinfunction "1_1") (pintype "passive"))
      (node (ref "R14") (pin "1") (pinfunction "1_1") (pintype "passive"))
    )
    (net (code "21") (name "Net-(1-IN_A-Pad3)") (class "Default")
      (node (ref "1") (pin "3") (pinfunction "IN_A_3") (pintype "input"))
      (node (ref "C12") (pin "2") (pinfunction "2_2") (pintype "passive"))
      (node (ref "R22") (pin "2") (pinfunction "2_2") (pintype "passive"))
    )
    (net (code "22") (name "Net-(1-IN_B-Pad5)") (class "Default")
      (node (ref "1") (pin "5") (pinfunction "IN_B_5") (pintype "input"))
      (node (ref "C13") (pin "1") (pinfunction "1_1") (pintype "passive"))
      (node (ref "R23") (pin "1") (pinfunction "1_1") (pintype "passive"))
    )
    (net (code "23") (name "Net-(1-IN_B-Pad6)") (class "Default")
      (node (ref "1") (pin "6") (pinfunction "IN_B_6") (pintype "input"))
      (node (ref "R13") (pin "1") (pinfunction "1_1") (pintype "passive"))
      (node (ref "R19") (pin "1") (pinfunction "1_1") (pintype "passive"))
    )
    (net (code "24") (name "Net-(2-IN_A-Pad2)") (class "Default")
      (node (ref "2") (pin "2") (pinfunction "IN_A_2") (pintype "input"))
      (node (ref "R47") (pin "1") (pinfunction "1_1") (pintype "passive"))
      (node (ref "R51") (pin "2") (pinfunction "2_2") (pintype "passive"))
    )
    (net (code "25") (name "Net-(2-IN_A-Pad3)") (class "Default")
      (node (ref "2") (pin "3") (pinfunction "IN_A_3") (pintype "input"))
      (node (ref "R48") (pin "1") (pinfunction "1_1") (pintype "passive"))
      (node (ref "R50") (pin "2") (pinfunction "2_2") (pintype "passive"))
    )
    (net (code "26") (name "Net-(2-IN_B-Pad5)") (class "Default")
      (node (ref "2") (pin "5") (pinfunction "IN_B_5") (pintype "input"))
      (node (ref "R36") (pin "1") (pinfunction "1_1") (pintype "passive"))
      (node (ref "R37") (pin "2") (pinfunction "2_2") (pintype "passive"))
    )
    (net (code "27") (name "Net-(2-IN_B-Pad6)") (class "Default")
      (node (ref "2") (pin "6") (pinfunction "IN_B_6") (pintype "input"))
      (node (ref "R17") (pin "2") (pinfunction "2_2") (pintype "passive"))
      (node (ref "R25") (pin "1") (pinfunction "1_1") (pintype "passive"))
    )
    (net (code "28") (name "Net-(2-OUT_A)") (class "Default")
      (node (ref "2") (pin "1") (pinfunction "OUT_A_1") (pintype "output"))
      (node (ref "C25") (pin "2") (pinfunction "2_2") (pintype "passive"))
      (node (ref "R47") (pin "2") (pinfunction "2_2") (pintype "passive"))
    )
    (net (code "29") (name "Net-(2-OUT_B)") (class "Default")
      (node (ref "2") (pin "7") (pinfunction "OUT_B_7") (pintype "output"))
      (node (ref "C15") (pin "2") (pinfunction "2_2") (pintype "passive"))
      (node (ref "R17") (pin "1") (pinfunction "1_1") (pintype "passive"))
    )
    (net (code "30") (name "Net-(3-IN_A-Pad2)") (class "Default")
      (node (ref "3") (pin "2") (pinfunction "IN_A_2") (pintype "input"))
      (node (ref "C1") (pin "1") (pinfunction "1_1") (pintype "passive"))
      (node (ref "R4") (pin "2") (pinfunction "2_2") (pintype "passive"))
      (node (ref "R6") (pin "2") (pinfunction "2_2") (pintype "passive"))
    )
    (net (code "31") (name "Net-(3-IN_A-Pad3)") (class "Default")
      (node (ref "3") (pin "3") (pinfunction "IN_A_3") (pintype "input"))
      (node (ref "C10") (pin "2") (pinfunction "2_2") (pintype "passive"))
      (node (ref "R10") (pin "2") (pinfunction "2_2") (pintype "passive"))
      (node (ref "R11") (pin "1") (pinfunction "1_1") (pintype "passive"))
    )
    (net (code "32") (name "Net-(3-IN_B-Pad5)") (class "Default")
      (node (ref "3") (pin "5") (pinfunction "IN_B_5") (pintype "input"))
      (node (ref "C9") (pin "1") (pinfunction "1_1") (pintype "passive"))
      (node (ref "R15") (pin "2") (pinfunction "2_2") (pintype "passive"))
      (node (ref "R16") (pin "1") (pinfunction "1_1") (pintype "passive"))
    )
    (net (code "33") (name "Net-(3-IN_B-Pad6)") (class "Default")
      (node (ref "3") (pin "6") (pinfunction "IN_B_6") (pintype "input"))
      (node (ref "C2") (pin "2") (pinfunction "2_2") (pintype "passive"))
      (node (ref "R5") (pin "2") (pinfunction "2_2") (pintype "passive"))
      (node (ref "R7") (pin "1") (pinfunction "1_1") (pintype "passive"))
    )
    (net (code "34") (name "Net-(3-OUT_A)") (class "Default")
      (node (ref "3") (pin "1") (pinfunction "OUT_A_1") (pintype "output"))
      (node (ref "R4") (pin "1") (pinfunction "1_1") (pintype "passive"))
    )
    (net (code "35") (name "Net-(3-OUT_B)") (class "Default")
      (node (ref "3") (pin "7") (pinfunction "OUT_B_7") (pintype "output"))
      (node (ref "R5") (pin "1") (pinfunction "1_1") (pintype "passive"))
    )
    (net (code "36") (name "Net-(C3-Pad2)") (class "Default")
      (node (ref "C3") (pin "2") (pinfunction "2_2") (pintype "passive"))
      (node (ref "R1") (pin "1") (pinfunction "1_1") (pintype "passive"))
      (node (ref "R6") (pin "1") (pinfunction "1_1") (pintype "passive"))
      (node (ref "R8") (pin "1") (pinfunction "1_1") (pintype "passive"))
    )
    (net (code "37") (name "Net-(C4-Pad1)") (class "Default")
      (node (ref "C4") (pin "1") (pinfunction "1_1") (pintype "passive"))
      (node (ref "R2") (pin "1") (pinfunction "1_1") (pintype "passive"))
      (node (ref "R7") (pin "2") (pinfunction "2_2") (pintype "passive"))
      (node (ref "R9") (pin "1") (pinfunction "1_1") (pintype "passive"))
    )
    (net (code "38") (name "Net-(C5-Pad2)") (class "Default")
      (node (ref "C5") (pin "2") (pinfunction "2_2") (pintype "passive"))
      (node (ref "L1") (pin "1") (pinfunction "1_1") (pintype "passive"))
    )
    (net (code "39") (name "Net-(C8-Pad2)") (class "Default")
      (node (ref "C8") (pin "2") (pinfunction "2_2") (pintype "passive"))
      (node (ref "R18") (pin "1") (pinfunction "1_1") (pintype "passive"))
      (node (ref "R21") (pin "1") (pinfunction "1_1") (pintype "passive"))
      (node (ref "R29") (pin "1") (pinfunction "1_1") (pintype "passive"))
    )
    (net (code "40") (name "Net-(C11-Pad1)") (class "Default")
      (node (ref "C11") (pin "1") (pinfunction "1_1") (pintype "passive"))
      (node (ref "R20") (pin "1") (pinfunction "1_1") (pintype "passive"))
      (node (ref "R26") (pin "2") (pinfunction "2_2") (pintype "passive"))
      (node (ref "R54") (pin "1") (pinfunction "1_1") (pintype "passive"))
    )
    (net (code "41") (name "Net-(C14-Pad1)") (class "Default")
      (node (ref "C14") (pin "1") (pinfunction "1_1") (pintype "passive"))
      (node (ref "R23") (pin "2") (pinfunction "2_2") (pintype "passive"))
      (node (ref "R26") (pin "1") (pinfunction "1_1") (pintype "passive"))
    )
    (net (code "42") (name "Net-(C16-Pad1)") (class "Default")
      (node (ref "C16") (pin "1") (pinfunction "1_1") (pintype "passive"))
      (node (ref "R25") (pin "2") (pinfunction "2_2") (pintype "passive"))
    )
    (net (code "43") (name "Net-(C17-Pad1)") (class "Default")
      (node (ref "C17") (pin "1") (pinfunction "1_1") (pintype "passive"))
      (node (ref "R21") (pin "2") (pinfunction "2_2") (pintype "passive"))
      (node (ref "R22") (pin "1") (pinfunction "1_1") (pintype "passive"))
    )
    (net (code "44") (name "Net-(C18-Pad1)") (class "Default")
      (node (ref "C18") (pin "1") (pinfunction "1_1") (pintype "passive"))
      (node (ref "C21") (pin "2") (pinfunction "2_2") (pintype "passive"))
      (node (ref "R30") (pin "1") (pinfunction "1_1") (pintype "passive"))
      (node (ref "R31") (pin "1") (pinfunction "1_1") (pintype "passive"))
      (node (ref "R32") (pin "2") (pinfunction "2_2") (pintype "passive"))
      (node (ref "R38") (pin "2") (pinfunction "2_2") (pintype "passive"))
    )
    (net (code "45") (name "Net-(C19-Pad1)") (class "Default")
      (node (ref "C19") (pin "1") (pinfunction "1_1") (pintype "passive"))
      (node (ref "R27") (pin "1") (pinfunction "1_1") (pintype "passive"))
      (node (ref "R36") (pin "2") (pinfunction "2_2") (pintype "passive"))
      (node (ref "R39") (pin "1") (pinfunction "1_1") (pintype "passive"))
    )
    (net (code "46") (name "Net-(C20-Pad1)") (class "Default")
      (node (ref "C20") (pin "1") (pinfunction "1_1") (pintype "passive"))
      (node (ref "C22") (pin "2") (pinfunction "2_2") (pintype "passive"))
      (node (ref "R35") (pin "1") (pinfunction "1_1") (pintype "passive"))
      (node (ref "R40") (pin "1") (pinfunction "1_1") (pintype "passive"))
      (node (ref "R43") (pin "2") (pinfunction "2_2") (pintype "passive"))
      (node (ref "R45") (pin "2") (pinfunction "2_2") (pintype "passive"))
    )
    (net (code "47") (name "Net-(C26-Pad1)") (class "Default")
      (node (ref "C26") (pin "1") (pinfunction "1_1") (pintype "passive"))
      (node (ref "R32") (pin "1") (pinfunction "1_1") (pintype "passive"))
      (node (ref "R42") (pin "1") (pinfunction "1_1") (pintype "passive"))
      (node (ref "R44") (pin "2") (pinfunction "2_2") (pintype "passive"))
      (node (ref "R46") (pin "1") (pinfunction "1_1") (pintype "passive"))
    )
    (net (code "48") (name "Net-(C27-Pad1)") (class "Default")
      (node (ref "C27") (pin "1") (pinfunction "1_1") (pintype "passive"))
      (node (ref "R43") (pin "1") (pinfunction "1_1") (pintype "passive"))
      (node (ref "R53") (pin "1") (pinfunction "1_1") (pintype "passive"))
      (node (ref "R55") (pin "2") (pinfunction "2_2") (pintype "passive"))
      (node (ref "R56") (pin "1") (pinfunction "1_1") (pintype "passive"))
    )
    (net (code "49") (name "Net-(C28-Pad1)") (class "Default")
      (node (ref "C28") (pin "1") (pinfunction "1_1") (pintype "passive"))
      (node (ref "R41") (pin "1") (pinfunction "1_1") (pintype "passive"))
      (node (ref "R48") (pin "2") (pinfunction "2_2") (pintype "passive"))
      (node (ref "R52") (pin "1") (pinfunction "1_1") (pintype "passive"))
    )
    (net (code "50") (name "Net-(C29-Pad1)") (class "Default")
      (node (ref "C29") (pin "1") (pinfunction "1_1") (pintype "passive"))
      (node (ref "R51") (pin "1") (pinfunction "1_1") (pintype "passive"))
    )
    (net (code "51") (name "Net-(Q1-B1_B4)") (class "Default")
      (node (ref "Q1") (pin "8") (pinfunction "B1_B4_8") (pintype "passive"))
      (node (ref "R38") (pin "1") (pinfunction "1_1") (pintype "passive"))
    )
    (net (code "52") (name "Net-(Q1-B2_B3)") (class "Default")
      (node (ref "C23") (pin "2") (pinfunction "2_2") (pintype "passive"))
      (node (ref "Q1") (pin "7") (pinfunction "B2_B3_7") (pintype "passive"))
      (node (ref "R31") (pin "2") (pinfunction "2_2") (pintype "passive"))
    )
    (net (code "53") (name "Net-(Q1-B5)") (class "Default")
      (node (ref "C30") (pin "2") (pinfunction "2_2") (pintype "passive"))
      (node (ref "Q1") (pin "1") (pinfunction "B5_1") (pintype "passive"))
      (node (ref "Q1") (pin "2") (pinfunction "E5_2") (pintype "passive"))
      (node (ref "Q1") (pin "3") (pinfunction "E6_3") (pintype "passive"))
      (node (ref "R46") (pin "2") (pinfunction "2_2") (pintype "passive"))
      (node (ref "R49") (pin "2") (pinfunction "2_2") (pintype "passive"))
    )
    (net (code "54") (name "Net-(Q1-B6)") (class "Default")
      (node (ref "Q1") (pin "4") (pinfunction "B6_4") (pintype "passive"))
      (node (ref "R42") (pin "2") (pinfunction "2_2") (pintype "passive"))
    )
    (net (code "55") (name "Net-(Q2-B1_B4)") (class "Default")
      (node (ref "Q2") (pin "8") (pinfunction "B1_B4_8") (pintype "passive"))
      (node (ref "R45") (pin "1") (pinfunction "1_1") (pintype "passive"))
    )
    (net (code "56") (name "Net-(Q2-B2_B3)") (class "Default")
      (node (ref "C24") (pin "2") (pinfunction "2_2") (pintype "passive"))
      (node (ref "Q2") (pin "7") (pinfunction "B2_B3_7") (pintype "passive"))
      (node (ref "R40") (pin "2") (pinfunction "2_2") (pintype "passive"))
    )
    (net (code "57") (name "Net-(Q2-B5)") (class "Default")
      (node (ref "C31") (pin "2") (pinfunction "2_2") (pintype "passive"))
      (node (ref "Q2") (pin "1") (pinfunction "B5_1") (pintype "passive"))
      (node (ref "Q2") (pin "2") (pinfunction "E5_2") (pintype "passive"))
      (node (ref "Q2") (pin "3") (pinfunction "E6_3") (pintype "passive"))
      (node (ref "R56") (pin "2") (pinfunction "2_2") (pintype "passive"))
      (node (ref "R57") (pin "2") (pinfunction "2_2") (pintype "passive"))
    )
    (net (code "58") (name "Net-(Q2-B6)") (class "Default")
      (node (ref "Q2") (pin "4") (pinfunction "B6_4") (pintype "passive"))
      (node (ref "R53") (pin "2") (pinfunction "2_2") (pintype "passive"))
    )
  )
)
